# ControllerV0.net
KiCad netlist of a schematic drawn in Altium Designer
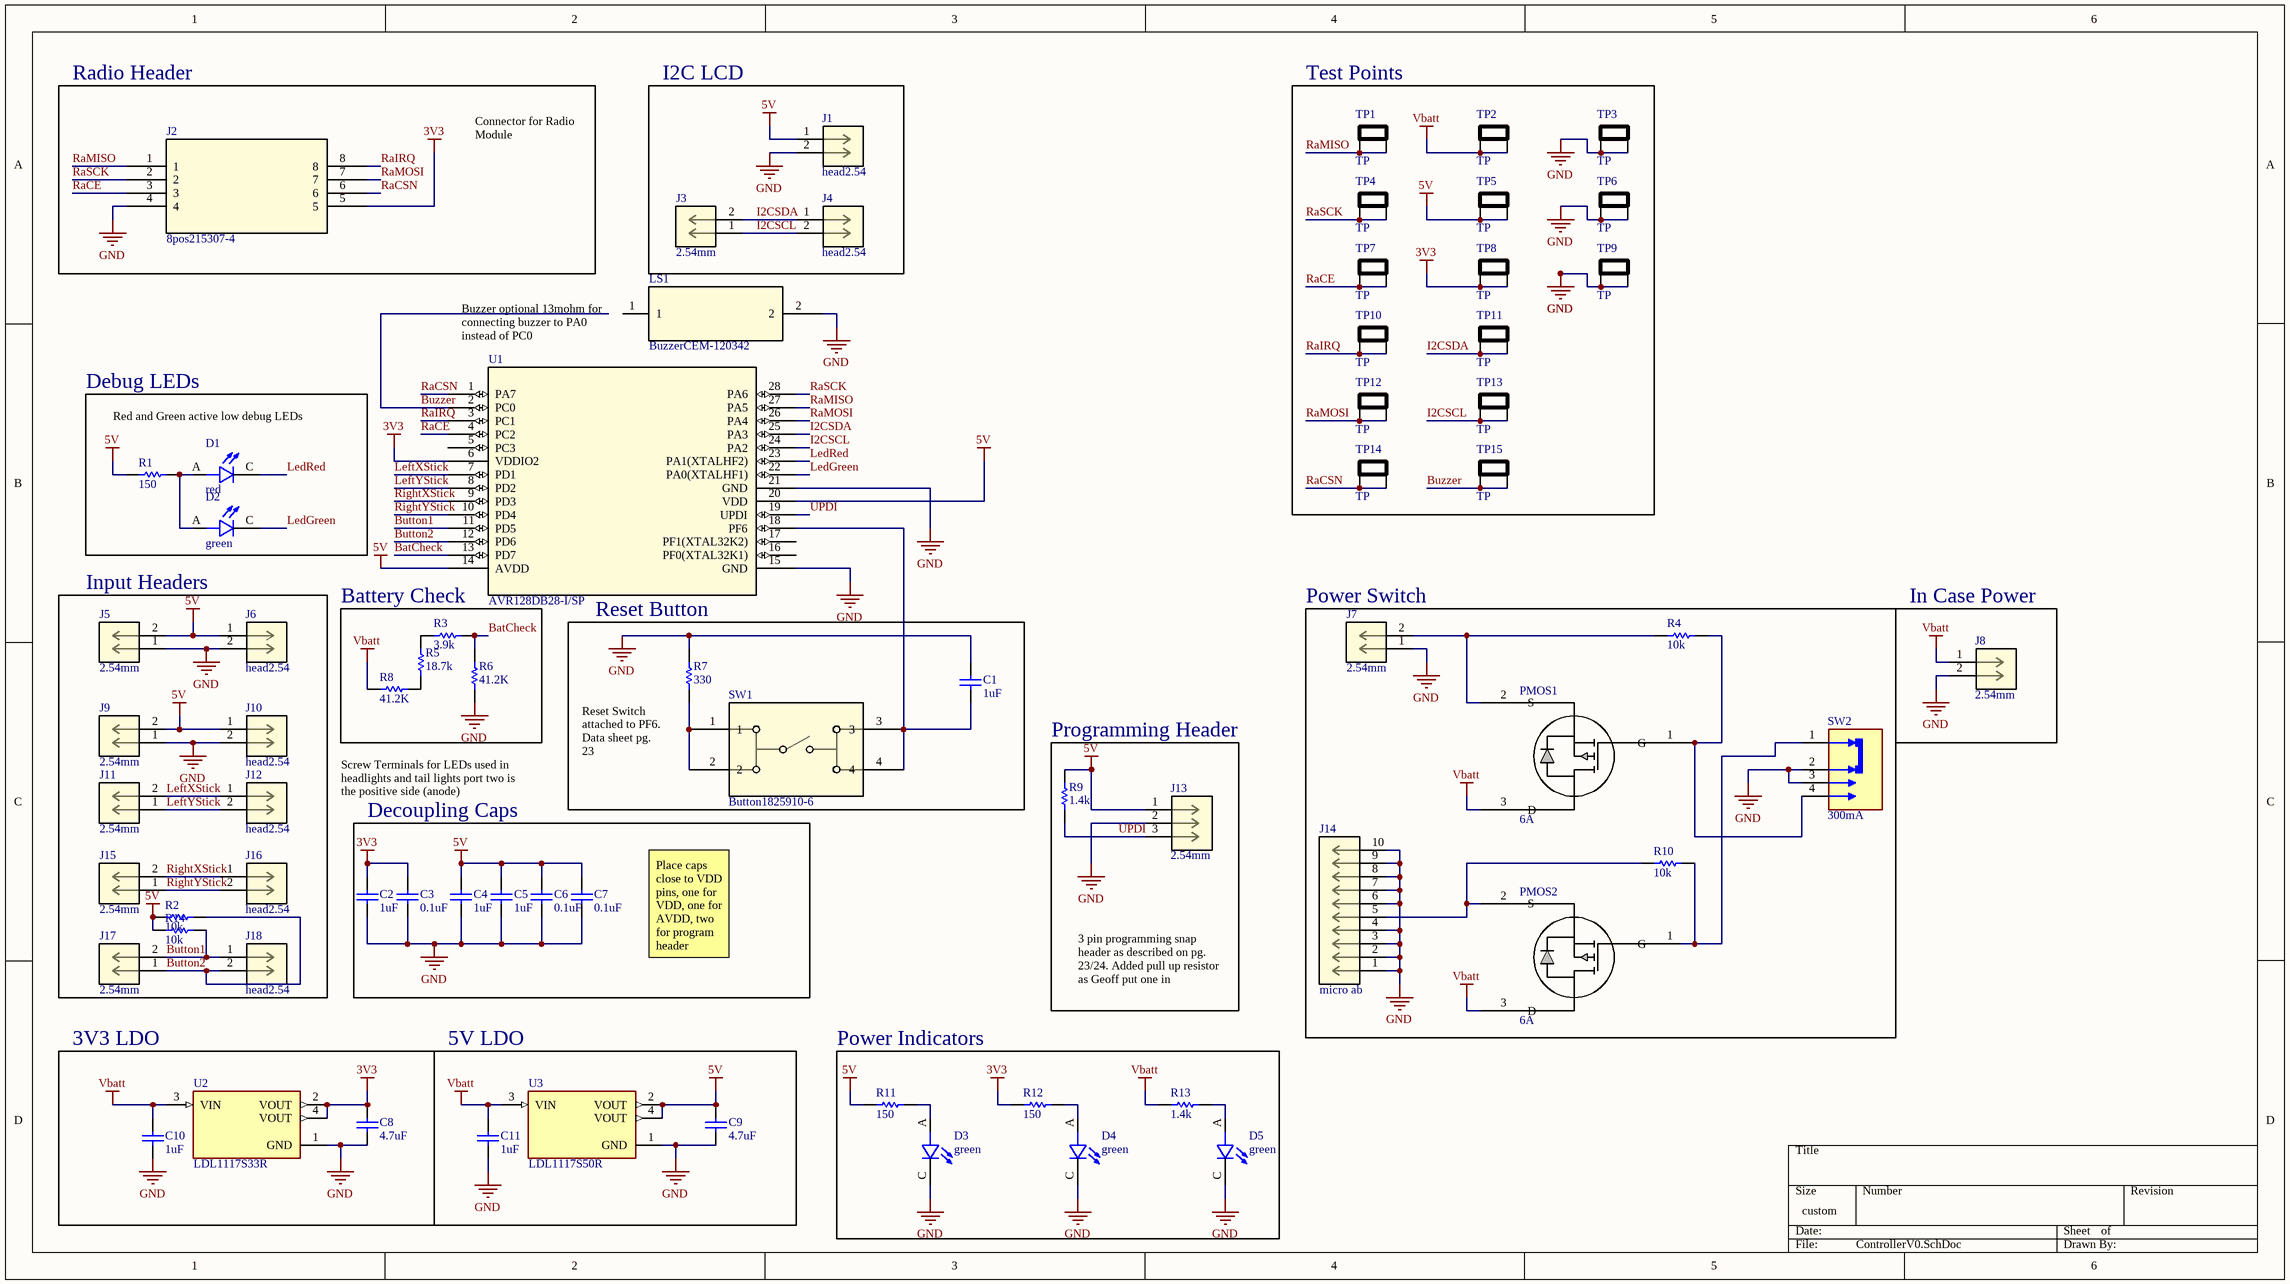
[diagram p0: ControllerV0.SchDoc]

(export (version "E")
  (design (tool "Eeschema 10.0.6"))
  (components
    (comp (ref "C1")
      (value "1uF")
      (footprint "RES 0805")
      (fields
        (field (name "MANUFACTURER") "Samsung")
        (field (name "MANUFACTURER PART NUMBER") "CL21B105KBFNNNE")
      )
      (libsource (lib "Schlib1") (part "CAP CER 1uF 10% 50V 0805"))
    )
    (comp (ref "C2")
      (value "1uF")
      (footprint "RES 0805")
      (fields
        (field (name "MANUFACTURER") "Samsung")
        (field (name "MANUFACTURER PART NUMBER") "CL21B105KBFNNNE")
      )
      (libsource (lib "Schlib1") (part "CAP CER 1uF 10% 50V 0805"))
    )
    (comp (ref "C3")
      (value "0.1uF")
      (footprint "RES 0805")
      (fields
        (field (name "MANUFACTURER") "Yageo")
        (field (name "MANUFACTURER PART NUMBER") "CC0805KRX7R9BB104")
      )
      (libsource (lib "Schlib1") (part "CAP CER 0.1uF 10% 50V 0805"))
    )
    (comp (ref "C4")
      (value "1uF")
      (footprint "RES 0805")
      (fields
        (field (name "MANUFACTURER") "Samsung")
        (field (name "MANUFACTURER PART NUMBER") "CL21B105KBFNNNE")
      )
      (libsource (lib "Schlib1") (part "CAP CER 1uF 10% 50V 0805"))
    )
    (comp (ref "C5")
      (value "1uF")
      (footprint "RES 0805")
      (fields
        (field (name "MANUFACTURER") "Samsung")
        (field (name "MANUFACTURER PART NUMBER") "CL21B105KBFNNNE")
      )
      (libsource (lib "Schlib1") (part "CAP CER 1uF 10% 50V 0805"))
    )
    (comp (ref "C6")
      (value "0.1uF")
      (footprint "RES 0805")
      (fields
        (field (name "MANUFACTURER") "Yageo")
        (field (name "MANUFACTURER PART NUMBER") "CC0805KRX7R9BB104")
      )
      (libsource (lib "Schlib1") (part "CAP CER 0.1uF 10% 50V 0805"))
    )
    (comp (ref "C7")
      (value "0.1uF")
      (footprint "RES 0805")
      (fields
        (field (name "MANUFACTURER") "Yageo")
        (field (name "MANUFACTURER PART NUMBER") "CC0805KRX7R9BB104")
      )
      (libsource (lib "Schlib1") (part "CAP CER 0.1uF 10% 50V 0805"))
    )
    (comp (ref "C8")
      (value "4.7uF")
      (footprint "RES 0805")
      (fields
        (field (name "MANUFACTURER") "Samsung")
        (field (name "MANUFACTURER PART NUMBER") "CL21A475KAQNNNE")
      )
      (libsource (lib "Schlib1") (part "CAP CER 4.7uF 10% 25V 0805"))
    )
    (comp (ref "C9")
      (value "4.7uF")
      (footprint "RES 0805")
      (fields
        (field (name "MANUFACTURER") "Samsung")
        (field (name "MANUFACTURER PART NUMBER") "CL21A475KAQNNNE")
      )
      (libsource (lib "Schlib1") (part "CAP CER 4.7uF 10% 25V 0805"))
    )
    (comp (ref "C10")
      (value "1uF")
      (footprint "RES 0805")
      (fields
        (field (name "MANUFACTURER") "Samsung")
        (field (name "MANUFACTURER PART NUMBER") "CL21B105KBFNNNE")
      )
      (libsource (lib "Schlib1") (part "CAP CER 1uF 10% 50V 0805"))
    )
    (comp (ref "C11")
      (value "1uF")
      (footprint "RES 0805")
      (fields
        (field (name "MANUFACTURER") "Samsung")
        (field (name "MANUFACTURER PART NUMBER") "CL21B105KBFNNNE")
      )
      (libsource (lib "Schlib1") (part "CAP CER 1uF 10% 50V 0805"))
    )
    (comp (ref "D1")
      (value "red")
      (footprint "0603LED")
      (description "Single Color LED, Red, Diffused Milky White, 1.2mm")
      (fields (field (name "MANUFACTURER") "Rohm") (field (name "MANUFACTURER PART NUMBER") "SML-D12U1WT86"))
      (libsource (lib "Schlib1") (part "LED redSML-D12U1WT86"))
    )
    (comp (ref "D2")
      (value "green")
      (footprint "0603LED")
      (description "Single Color LED, Pure Green, Diffused Milky White, 1.2mm")
      (fields (field (name "MANUFACTURER") "Rohm") (field (name "MANUFACTURER PART NUMBER") "SML-D12P8WT86"))
      (libsource (lib "Schlib1") (part "LED greenSML-D12P8WT86"))
    )
    (comp (ref "D3")
      (value "green")
      (footprint "0603LED")
      (description "Single Color LED, Pure Green, Diffused Milky White, 1.2mm")
      (fields (field (name "MANUFACTURER") "Rohm") (field (name "MANUFACTURER PART NUMBER") "SML-D12P8WT86"))
      (libsource (lib "Schlib1") (part "LED greenSML-D12P8WT86"))
    )
    (comp (ref "D4")
      (value "green")
      (footprint "0603LED")
      (description "Single Color LED, Pure Green, Diffused Milky White, 1.2mm")
      (fields (field (name "MANUFACTURER") "Rohm") (field (name "MANUFACTURER PART NUMBER") "SML-D12P8WT86"))
      (libsource (lib "Schlib1") (part "LED greenSML-D12P8WT86"))
    )
    (comp (ref "D5")
      (value "green")
      (footprint "0603LED")
      (description "Single Color LED, Pure Green, Diffused Milky White, 1.2mm")
      (fields (field (name "MANUFACTURER") "Rohm") (field (name "MANUFACTURER PART NUMBER") "SML-D12P8WT86"))
      (libsource (lib "Schlib1") (part "LED greenSML-D12P8WT86"))
    )
    (comp (ref "J1")
      (value "head2.54")
      (footprint "Head 2.54mm 2pos")
      (fields (field (name "MANUFACTURER") "Samtec") (field (name "MANUFACTURER PART NUMBER") "TS-102-G-AA"))
      (libsource (lib "Schlib1") (part "HEAD 2.54mm 2pos"))
    )
    (comp (ref "J2")
      (value "8pos215307-4")
      (footprint "215307-4")
      (fields
        (field (name "MANUFACTURER") "TE Connectivity")
        (field (name "MANUFACTURER PART NUMBER") "215307-4")
      )
      (libsource (lib "Schlib1") (part "8pos215307-4"))
    )
    (comp (ref "J3")
      (value "2.54mm")
      (footprint "CON screw 2pos 2.54mm")
      (description "Barrier Strip Terminal Block, 6A, 1 Row(s), 1 Deck(s)")
      (fields
        (field (name "MANUFACTURER") "On-Shore Technology")
        (field (name "MANUFACTURER PART NUMBER") "OSTVN02A150")
        (field (name "SAFETY APPROVAL") "UL,CUL")
      )
      (libsource (lib "Schlib1") (part "CON screw 2pos 2.54mm"))
    )
    (comp (ref "J4")
      (value "head2.54")
      (footprint "Head 2.54mm 2pos")
      (fields (field (name "MANUFACTURER") "Samtec") (field (name "MANUFACTURER PART NUMBER") "TS-102-G-AA"))
      (libsource (lib "Schlib1") (part "HEAD 2.54mm 2pos"))
    )
    (comp (ref "J5")
      (value "2.54mm")
      (footprint "CON screw 2pos 2.54mm")
      (description "Barrier Strip Terminal Block, 6A, 1 Row(s), 1 Deck(s)")
      (fields
        (field (name "MANUFACTURER") "On-Shore Technology")
        (field (name "MANUFACTURER PART NUMBER") "OSTVN02A150")
        (field (name "SAFETY APPROVAL") "UL,CUL")
      )
      (libsource (lib "Schlib1") (part "CON screw 2pos 2.54mm"))
    )
    (comp (ref "J6")
      (value "head2.54")
      (footprint "Head 2.54mm 2pos")
      (fields (field (name "MANUFACTURER") "Samtec") (field (name "MANUFACTURER PART NUMBER") "TS-102-G-AA"))
      (libsource (lib "Schlib1") (part "HEAD 2.54mm 2pos"))
    )
    (comp (ref "J7")
      (value "2.54mm")
      (footprint "CON screw 2pos 2.54mm")
      (description "Barrier Strip Terminal Block, 6A, 1 Row(s), 1 Deck(s)")
      (fields
        (field (name "MANUFACTURER") "On-Shore Technology")
        (field (name "MANUFACTURER PART NUMBER") "OSTVN02A150")
        (field (name "SAFETY APPROVAL") "UL,CUL")
      )
      (libsource (lib "Schlib1") (part "CON screw 2pos 2.54mm"))
    )
    (comp (ref "J8")
      (value "2.54mm")
      (footprint "CON screw 2pos 2.54mm")
      (description "Barrier Strip Terminal Block, 6A, 1 Row(s), 1 Deck(s)")
      (fields
        (field (name "MANUFACTURER") "On-Shore Technology")
        (field (name "MANUFACTURER PART NUMBER") "OSTVN02A150")
        (field (name "SAFETY APPROVAL") "UL,CUL")
      )
      (libsource (lib "") (part "CON screw 2pos 2.54mm_1"))
    )
    (comp (ref "J9")
      (value "2.54mm")
      (footprint "CON screw 2pos 2.54mm")
      (description "Barrier Strip Terminal Block, 6A, 1 Row(s), 1 Deck(s)")
      (fields
        (field (name "MANUFACTURER") "On-Shore Technology")
        (field (name "MANUFACTURER PART NUMBER") "OSTVN02A150")
        (field (name "SAFETY APPROVAL") "UL,CUL")
      )
      (libsource (lib "Schlib1") (part "CON screw 2pos 2.54mm"))
    )
    (comp (ref "J10")
      (value "head2.54")
      (footprint "Head 2.54mm 2pos")
      (fields (field (name "MANUFACTURER") "Samtec") (field (name "MANUFACTURER PART NUMBER") "TS-102-G-AA"))
      (libsource (lib "Schlib1") (part "HEAD 2.54mm 2pos"))
    )
    (comp (ref "J11")
      (value "2.54mm")
      (footprint "CON screw 2pos 2.54mm")
      (description "Barrier Strip Terminal Block, 6A, 1 Row(s), 1 Deck(s)")
      (fields
        (field (name "MANUFACTURER") "On-Shore Technology")
        (field (name "MANUFACTURER PART NUMBER") "OSTVN02A150")
        (field (name "SAFETY APPROVAL") "UL,CUL")
      )
      (libsource (lib "Schlib1") (part "CON screw 2pos 2.54mm"))
    )
    (comp (ref "J12")
      (value "head2.54")
      (footprint "Head 2.54mm 2pos")
      (fields (field (name "MANUFACTURER") "Samtec") (field (name "MANUFACTURER PART NUMBER") "TS-102-G-AA"))
      (libsource (lib "Schlib1") (part "HEAD 2.54mm 2pos"))
    )
    (comp (ref "J13")
      (value "2.54mm")
      (footprint "HEAD 2.54mm 3pos")
      (fields (field (name "MANUFACTURER") "Samtec") (field (name "MANUFACTURER PART NUMBER") "TS-103-T-A"))
      (libsource (lib "Schlib1") (part "HEAD 2.54mm 3pos"))
    )
    (comp (ref "J14")
      (value "micro ab")
      (footprint "USB micro ab 0475900001")
      (description "USB Connector, 5 Contact(s), Female, Right Angle, Surface Mount Terminal, Locking, Receptacle")
      (fields (field (name "MANUFACTURER") "Molex") (field (name "MANUFACTURER PART NUMBER") "47590-0001"))
      (libsource (lib "Schlib1") (part "CON USB micro ab"))
    )
    (comp (ref "J15")
      (value "2.54mm")
      (footprint "CON screw 2pos 2.54mm")
      (description "Barrier Strip Terminal Block, 6A, 1 Row(s), 1 Deck(s)")
      (fields
        (field (name "MANUFACTURER") "On-Shore Technology")
        (field (name "MANUFACTURER PART NUMBER") "OSTVN02A150")
        (field (name "SAFETY APPROVAL") "UL,CUL")
      )
      (libsource (lib "Schlib1") (part "CON screw 2pos 2.54mm"))
    )
    (comp (ref "J16")
      (value "head2.54")
      (footprint "Head 2.54mm 2pos")
      (fields (field (name "MANUFACTURER") "Samtec") (field (name "MANUFACTURER PART NUMBER") "TS-102-G-AA"))
      (libsource (lib "Schlib1") (part "HEAD 2.54mm 2pos"))
    )
    (comp (ref "J17")
      (value "2.54mm")
      (footprint "CON screw 2pos 2.54mm")
      (description "Barrier Strip Terminal Block, 6A, 1 Row(s), 1 Deck(s)")
      (fields
        (field (name "MANUFACTURER") "On-Shore Technology")
        (field (name "MANUFACTURER PART NUMBER") "OSTVN02A150")
        (field (name "SAFETY APPROVAL") "UL,CUL")
      )
      (libsource (lib "Schlib1") (part "CON screw 2pos 2.54mm"))
    )
    (comp (ref "J18")
      (value "head2.54")
      (footprint "Head 2.54mm 2pos")
      (fields (field (name "MANUFACTURER") "Samtec") (field (name "MANUFACTURER PART NUMBER") "TS-102-G-AA"))
      (libsource (lib "Schlib1") (part "HEAD 2.54mm 2pos"))
    )
    (comp (ref "LS1")
      (value "BuzzerCEM-120342")
      (footprint "CEM-1203(42)")
      (description "Audio Signaling/Alarm Devices")
      (fields
        (field (name "MANUFACTURER") "CUI Devices")
        (field (name "MANUFACTURER PART NUMBER") "CEM-1203(42)")
      )
      (libsource (lib "Schlib1") (part "BuzzerCEM-120342"))
    )
    (comp (ref "PMOS1")
      (value "6A")
      (footprint "SOT-23F MOS PMOS 30V 6A")
      (fields
        (field (name "MANUFACTURER") "Toshiba")
        (field (name "MANUFACTURER PART NUMBER") "SSM3J372R,LF")
      )
      (libsource (lib "Schlib1") (part "MOS PMOS 30V 6A"))
    )
    (comp (ref "PMOS2")
      (value "6A")
      (footprint "SOT-23F MOS PMOS 30V 6A")
      (fields
        (field (name "MANUFACTURER") "Toshiba")
        (field (name "MANUFACTURER PART NUMBER") "SSM3J372R,LF")
      )
      (libsource (lib "Schlib1") (part "MOS PMOS 30V 6A"))
    )
    (comp (ref "R1")
      (value "150")
      (footprint "RES 0805")
      (fields
        (field (name "MANUFACTURER") "Yageo")
        (field (name "MANUFACTURER PART NUMBER") "RC0805FR-07150RL")
        (field (name "TOLERANCE") "1%")
      )
      (libsource (lib "Schlib1") (part "RES 150 1% 0.125 0805"))
    )
    (comp (ref "R2")
      (value "10k")
      (footprint "RES 0805")
      (fields
        (field (name "MANUFACTURER") "Stackpole Electronics")
        (field (name "MANUFACTURER PART NUMBER") "RMCF0805FT10K0")
        (field (name "TOLERANCE") "1%")
      )
      (libsource (lib "Schlib1") (part "RES 10k 1% 0.125 0805"))
    )
    (comp (ref "R3")
      (value "3.9k")
      (footprint "RES 0805")
      (fields
        (field (name "MANUFACTURER") "Stackpole Electronics")
        (field (name "MANUFACTURER PART NUMBER") "RMCF0805FT3K92")
        (field (name "TOLERANCE") "1%")
      )
      (libsource (lib "Schlib1") (part "RES 3.9k 1% 0.125W 0805"))
    )
    (comp (ref "R4")
      (value "10k")
      (footprint "RES 0805")
      (fields
        (field (name "MANUFACTURER") "Stackpole Electronics")
        (field (name "MANUFACTURER PART NUMBER") "RMCF0805FT10K0")
        (field (name "TOLERANCE") "1%")
      )
      (libsource (lib "Schlib1") (part "RES 10k 1% 0.125 0805"))
    )
    (comp (ref "R5")
      (value "18.7k")
      (footprint "RES 0805")
      (fields
        (field (name "MANUFACTURER") "Stackpole Electronics")
        (field (name "MANUFACTURER PART NUMBER") "RMCF0805FT18K7")
        (field (name "TOLERANCE") "1%")
      )
      (libsource (lib "Schlib1") (part "RES 18.7k 1% 0.125W 0805"))
    )
    (comp (ref "R6")
      (value "41.2K")
      (footprint "RES 0805")
      (fields
        (field (name "MANUFACTURER") "Vishay")
        (field (name "MANUFACTURER PART NUMBER") "CRCW080541K2FKEA")
        (field (name "TOLERANCE") "1%")
      )
      (libsource (lib "Schlib1") (part "RES 41.2K 1% 0.125W 0805"))
    )
    (comp (ref "R7")
      (value "330")
      (footprint "RES 0805")
      (fields
        (field (name "MANUFACTURER") "Stackpole Electronics")
        (field (name "MANUFACTURER PART NUMBER") "RMCF0805FT330R")
        (field (name "TOLERANCE") "1%")
      )
      (libsource (lib "Schlib1") (part "RES 330 1% 0.125W 0805"))
    )
    (comp (ref "R8")
      (value "41.2K")
      (footprint "RES 0805")
      (fields
        (field (name "MANUFACTURER") "Vishay")
        (field (name "MANUFACTURER PART NUMBER") "CRCW080541K2FKEA")
        (field (name "TOLERANCE") "1%")
      )
      (libsource (lib "Schlib1") (part "RES 41.2K 1% 0.125W 0805"))
    )
    (comp (ref "R9")
      (value "1.4k")
      (footprint "RES 0805")
      (fields
        (field (name "MANUFACTURER") "Yageo")
        (field (name "MANUFACTURER PART NUMBER") "RC0805FR-071K4L")
        (field (name "TOLERANCE") "1%")
      )
      (libsource (lib "Schlib1") (part "RES 1.4k 1% 0.125W 0805"))
    )
    (comp (ref "R10")
      (value "10k")
      (footprint "RES 0805")
      (fields
        (field (name "MANUFACTURER") "Stackpole Electronics")
        (field (name "MANUFACTURER PART NUMBER") "RMCF0805FT10K0")
        (field (name "TOLERANCE") "1%")
      )
      (libsource (lib "Schlib1") (part "RES 10k 1% 0.125 0805"))
    )
    (comp (ref "R11")
      (value "150")
      (footprint "RES 0805")
      (fields
        (field (name "MANUFACTURER") "Yageo")
        (field (name "MANUFACTURER PART NUMBER") "RC0805FR-07150RL")
        (field (name "TOLERANCE") "1%")
      )
      (libsource (lib "Schlib1") (part "RES 150 1% 0.125 0805"))
    )
    (comp (ref "R12")
      (value "150")
      (footprint "RES 0805")
      (fields
        (field (name "MANUFACTURER") "Yageo")
        (field (name "MANUFACTURER PART NUMBER") "RC0805FR-07150RL")
        (field (name "TOLERANCE") "1%")
      )
      (libsource (lib "Schlib1") (part "RES 150 1% 0.125 0805"))
    )
    (comp (ref "R13")
      (value "1.4k")
      (footprint "RES 0805")
      (fields
        (field (name "MANUFACTURER") "Yageo")
        (field (name "MANUFACTURER PART NUMBER") "RC0805FR-071K4L")
        (field (name "TOLERANCE") "1%")
      )
      (libsource (lib "Schlib1") (part "RES 1.4k 1% 0.125W 0805"))
    )
    (comp (ref "R14")
      (value "10k")
      (footprint "RES 0805")
      (fields
        (field (name "MANUFACTURER") "Stackpole Electronics")
        (field (name "MANUFACTURER PART NUMBER") "RMCF0805FT10K0")
        (field (name "TOLERANCE") "1%")
      )
      (libsource (lib "Schlib1") (part "RES 10k 1% 0.125 0805"))
    )
    (comp (ref "SW1")
      (value "Button1825910-6")
      (footprint "Button1825910-6")
      (fields
        (field (name "MANUFACTURER") "TE Connectivity Alcoswitch")
        (field (name "MANUFACTURER PART NUMBER") "1825910-6")
      )
      (libsource (lib "Schlib1") (part "Button1825910-6"))
    )
    (comp (ref "SW2")
      (value "300mA")
      (footprint "Switch On-On-On 300mA SLW-1277545-2A-RA-S-D")
      (description "12.7 x 7.5 x 4.5 mm, 2 mm Raised Slide Actuator, Right Angle, Through Hole, Slide Switch")
      (fields
        (field (name "MANUFACTURER") "Same Sky")
        (field (name "MANUFACTURER PART NUMBER") "SLW-1277545-2A-RA-S-D")
      )
      (libsource (lib "Schlib1") (part "SW On-On-On 300mA"))
    )
    (comp (ref "TP1")
      (value "TP")
      (footprint "RES 0805")
      (description "Testing/Accessories")
      (fields (field (name "MANUFACTURER") "KOA Speer") (field (name "MANUFACTURER PART NUMBER") "RCTCTE"))
      (libsource (lib "Schlib1") (part "TP clip 0805 RCTCTE"))
    )
    (comp (ref "TP2")
      (value "TP")
      (footprint "RES 0805")
      (description "Testing/Accessories")
      (fields (field (name "MANUFACTURER") "KOA Speer") (field (name "MANUFACTURER PART NUMBER") "RCTCTE"))
      (libsource (lib "Schlib1") (part "TP clip 0805 RCTCTE"))
    )
    (comp (ref "TP3")
      (value "TP")
      (footprint "RES 0805")
      (description "Testing/Accessories")
      (fields (field (name "MANUFACTURER") "KOA Speer") (field (name "MANUFACTURER PART NUMBER") "RCTCTE"))
      (libsource (lib "Schlib1") (part "TP clip 0805 RCTCTE"))
    )
    (comp (ref "TP4")
      (value "TP")
      (footprint "RES 0805")
      (description "Testing/Accessories")
      (fields (field (name "MANUFACTURER") "KOA Speer") (field (name "MANUFACTURER PART NUMBER") "RCTCTE"))
      (libsource (lib "Schlib1") (part "TP clip 0805 RCTCTE"))
    )
    (comp (ref "TP5")
      (value "TP")
      (footprint "RES 0805")
      (description "Testing/Accessories")
      (fields (field (name "MANUFACTURER") "KOA Speer") (field (name "MANUFACTURER PART NUMBER") "RCTCTE"))
      (libsource (lib "Schlib1") (part "TP clip 0805 RCTCTE"))
    )
    (comp (ref "TP6")
      (value "TP")
      (footprint "RES 0805")
      (description "Testing/Accessories")
      (fields (field (name "MANUFACTURER") "KOA Speer") (field (name "MANUFACTURER PART NUMBER") "RCTCTE"))
      (libsource (lib "Schlib1") (part "TP clip 0805 RCTCTE"))
    )
    (comp (ref "TP7")
      (value "TP")
      (footprint "RES 0805")
      (description "Testing/Accessories")
      (fields (field (name "MANUFACTURER") "KOA Speer") (field (name "MANUFACTURER PART NUMBER") "RCTCTE"))
      (libsource (lib "Schlib1") (part "TP clip 0805 RCTCTE"))
    )
    (comp (ref "TP8")
      (value "TP")
      (footprint "RES 0805")
      (description "Testing/Accessories")
      (fields (field (name "MANUFACTURER") "KOA Speer") (field (name "MANUFACTURER PART NUMBER") "RCTCTE"))
      (libsource (lib "Schlib1") (part "TP clip 0805 RCTCTE"))
    )
    (comp (ref "TP9")
      (value "TP")
      (footprint "RES 0805")
      (description "Testing/Accessories")
      (fields (field (name "MANUFACTURER") "KOA Speer") (field (name "MANUFACTURER PART NUMBER") "RCTCTE"))
      (libsource (lib "Schlib1") (part "TP clip 0805 RCTCTE"))
    )
    (comp (ref "TP10")
      (value "TP")
      (footprint "RES 0805")
      (description "Testing/Accessories")
      (fields (field (name "MANUFACTURER") "KOA Speer") (field (name "MANUFACTURER PART NUMBER") "RCTCTE"))
      (libsource (lib "Schlib1") (part "TP clip 0805 RCTCTE"))
    )
    (comp (ref "TP11")
      (value "TP")
      (footprint "RES 0805")
      (description "Testing/Accessories")
      (fields (field (name "MANUFACTURER") "KOA Speer") (field (name "MANUFACTURER PART NUMBER") "RCTCTE"))
      (libsource (lib "Schlib1") (part "TP clip 0805 RCTCTE"))
    )
    (comp (ref "TP12")
      (value "TP")
      (footprint "RES 0805")
      (description "Testing/Accessories")
      (fields (field (name "MANUFACTURER") "KOA Speer") (field (name "MANUFACTURER PART NUMBER") "RCTCTE"))
      (libsource (lib "Schlib1") (part "TP clip 0805 RCTCTE"))
    )
    (comp (ref "TP13")
      (value "TP")
      (footprint "RES 0805")
      (description "Testing/Accessories")
      (fields (field (name "MANUFACTURER") "KOA Speer") (field (name "MANUFACTURER PART NUMBER") "RCTCTE"))
      (libsource (lib "Schlib1") (part "TP clip 0805 RCTCTE"))
    )
    (comp (ref "TP14")
      (value "TP")
      (footprint "RES 0805")
      (description "Testing/Accessories")
      (fields (field (name "MANUFACTURER") "KOA Speer") (field (name "MANUFACTURER PART NUMBER") "RCTCTE"))
      (libsource (lib "Schlib1") (part "TP clip 0805 RCTCTE"))
    )
    (comp (ref "TP15")
      (value "TP")
      (footprint "RES 0805")
      (description "Testing/Accessories")
      (fields (field (name "MANUFACTURER") "KOA Speer") (field (name "MANUFACTURER PART NUMBER") "RCTCTE"))
      (libsource (lib "Schlib1") (part "TP clip 0805 RCTCTE"))
    )
    (comp (ref "U1")
      (value "AVR128DB28-I/SP")
      (footprint "AVR128DB28-ISP")
      (description "RISC Microcontroller, 8-Bit, FLASH, AVR CPU, 24MHz, CMOS, PDIP28")
      (fields (field (name "MANUFACTURER") "Microchip"))
      (libsource (lib "Schlib1") (part "AVR128DB28-I/SP"))
    )
    (comp (ref "U2")
      (value "LDL1117S33R")
      (footprint "SOT230P700X180-4N")
      (description "Fixed Positive LDO Regulator, 3.3V, 0.6V Dropout, PDSO4")
      (fields (field (name "MANUFACTURER") "STMicroelectronics"))
      (libsource (lib "Schlib1") (part "LDL1117S33R"))
    )
    (comp (ref "U3")
      (value "LDL1117S50R")
      (footprint "SOT230P700X180-4N")
      (description "Fixed Positive LDO Regulator, 5V, 0.6V Dropout, PDSO4")
      (fields (field (name "MANUFACTURER") "STMicroelectronics"))
      (libsource (lib "Schlib1") (part "LDL1117S50R"))
    )
  )
  (nets
    (net (code "1") (name "/BatCheck") (class "Default")
      (node (ref "R3") (pin "2") (pinfunction "2_2") (pintype "passive"))
      (node (ref "R6") (pin "2") (pinfunction "2_2") (pintype "passive"))
      (node (ref "U1") (pin "13") (pinfunction "PD7_13") (pintype "bidirectional"))
    )
    (net (code "2") (name "/Button1") (class "Default")
      (node (ref "J17") (pin "2") (pinfunction "2_2") (pintype "passive"))
      (node (ref "J18") (pin "1") (pinfunction "1_1") (pintype "passive"))
      (node (ref "R14") (pin "1") (pinfunction "1_1") (pintype "passive"))
      (node (ref "U1") (pin "11") (pinfunction "PD5_11") (pintype "bidirectional"))
    )
    (net (code "3") (name "/Button2") (class "Default")
      (node (ref "J17") (pin "1") (pinfunction "1_1") (pintype "passive"))
      (node (ref "J18") (pin "2") (pinfunction "2_2") (pintype "passive"))
      (node (ref "R2") (pin "1") (pinfunction "1_1") (pintype "passive"))
      (node (ref "U1") (pin "12") (pinfunction "PD6_12") (pintype "bidirectional"))
    )
    (net (code "4") (name "/Buzzer") (class "Default")
      (node (ref "LS1") (pin "1") (pinfunction "1_1") (pintype "passive"))
      (node (ref "TP15") (pin "1") (pinfunction "1_1") (pintype "passive"))
      (node (ref "TP15") (pin "2") (pinfunction "2_2") (pintype "passive"))
      (node (ref "U1") (pin "2") (pinfunction "PC0_2") (pintype "bidirectional"))
    )
    (net (code "5") (name "/I2CSCL") (class "Default")
      (node (ref "J3") (pin "1") (pinfunction "1_1") (pintype "passive"))
      (node (ref "J4") (pin "2") (pinfunction "2_2") (pintype "passive"))
      (node (ref "TP13") (pin "1") (pinfunction "1_1") (pintype "passive"))
      (node (ref "TP13") (pin "2") (pinfunction "2_2") (pintype "passive"))
      (node (ref "U1") (pin "24") (pinfunction "PA2_24") (pintype "bidirectional"))
    )
    (net (code "6") (name "/I2CSDA") (class "Default")
      (node (ref "J3") (pin "2") (pinfunction "2_2") (pintype "passive"))
      (node (ref "J4") (pin "1") (pinfunction "1_1") (pintype "passive"))
      (node (ref "TP11") (pin "1") (pinfunction "1_1") (pintype "passive"))
      (node (ref "TP11") (pin "2") (pinfunction "2_2") (pintype "passive"))
      (node (ref "U1") (pin "25") (pinfunction "PA3_25") (pintype "bidirectional"))
    )
    (net (code "7") (name "/LedGreen") (class "Default")
      (node (ref "D2") (pin "C") (pinfunction "C_C") (pintype "passive"))
      (node (ref "U1") (pin "22") (pinfunction "PA0(XTALHF1)_22") (pintype "bidirectional"))
    )
    (net (code "8") (name "/LedRed") (class "Default")
      (node (ref "D1") (pin "C") (pinfunction "C_C") (pintype "passive"))
      (node (ref "U1") (pin "23") (pinfunction "PA1(XTALHF2)_23") (pintype "bidirectional"))
    )
    (net (code "9") (name "/LeftXStick") (class "Default")
      (node (ref "J11") (pin "2") (pinfunction "2_2") (pintype "passive"))
      (node (ref "J12") (pin "1") (pinfunction "1_1") (pintype "passive"))
      (node (ref "U1") (pin "7") (pinfunction "PD1_7") (pintype "bidirectional"))
    )
    (net (code "10") (name "/LeftYStick") (class "Default")
      (node (ref "J11") (pin "1") (pinfunction "1_1") (pintype "passive"))
      (node (ref "J12") (pin "2") (pinfunction "2_2") (pintype "passive"))
      (node (ref "U1") (pin "8") (pinfunction "PD2_8") (pintype "bidirectional"))
    )
    (net (code "11") (name "/RaCE") (class "Default")
      (node (ref "J2") (pin "3") (pinfunction "3_3") (pintype "passive"))
      (node (ref "TP7") (pin "1") (pinfunction "1_1") (pintype "passive"))
      (node (ref "TP7") (pin "2") (pinfunction "2_2") (pintype "passive"))
      (node (ref "U1") (pin "4") (pinfunction "PC2_4") (pintype "bidirectional"))
    )
    (net (code "12") (name "/RaCSN") (class "Default")
      (node (ref "J2") (pin "6") (pinfunction "6_6") (pintype "passive"))
      (node (ref "TP14") (pin "1") (pinfunction "1_1") (pintype "passive"))
      (node (ref "TP14") (pin "2") (pinfunction "2_2") (pintype "passive"))
      (node (ref "U1") (pin "1") (pinfunction "PA7_1") (pintype "bidirectional"))
    )
    (net (code "13") (name "/RaIRQ") (class "Default")
      (node (ref "J2") (pin "8") (pinfunction "8_8") (pintype "passive"))
      (node (ref "TP10") (pin "1") (pinfunction "1_1") (pintype "passive"))
      (node (ref "TP10") (pin "2") (pinfunction "2_2") (pintype "passive"))
      (node (ref "U1") (pin "3") (pinfunction "PC1_3") (pintype "bidirectional"))
    )
    (net (code "14") (name "/RaMISO") (class "Default")
      (node (ref "J2") (pin "1") (pinfunction "1_1") (pintype "passive"))
      (node (ref "TP1") (pin "1") (pinfunction "1_1") (pintype "passive"))
      (node (ref "TP1") (pin "2") (pinfunction "2_2") (pintype "passive"))
      (node (ref "U1") (pin "27") (pinfunction "PA5_27") (pintype "bidirectional"))
    )
    (net (code "15") (name "/RaMOSI") (class "Default")
      (node (ref "J2") (pin "7") (pinfunction "7_7") (pintype "passive"))
      (node (ref "TP12") (pin "1") (pinfunction "1_1") (pintype "passive"))
      (node (ref "TP12") (pin "2") (pinfunction "2_2") (pintype "passive"))
      (node (ref "U1") (pin "26") (pinfunction "PA4_26") (pintype "bidirectional"))
    )
    (net (code "16") (name "/RaSCK") (class "Default")
      (node (ref "J2") (pin "2") (pinfunction "2_2") (pintype "passive"))
      (node (ref "TP4") (pin "1") (pinfunction "1_1") (pintype "passive"))
      (node (ref "TP4") (pin "2") (pinfunction "2_2") (pintype "passive"))
      (node (ref "U1") (pin "28") (pinfunction "PA6_28") (pintype "bidirectional"))
    )
    (net (code "17") (name "/RightXStick") (class "Default")
      (node (ref "J15") (pin "2") (pinfunction "2_2") (pintype "passive"))
      (node (ref "J16") (pin "1") (pinfunction "1_1") (pintype "passive"))
      (node (ref "U1") (pin "9") (pinfunction "PD3_9") (pintype "bidirectional"))
    )
    (net (code "18") (name "/RightYStick") (class "Default")
      (node (ref "J15") (pin "1") (pinfunction "1_1") (pintype "passive"))
      (node (ref "J16") (pin "2") (pinfunction "2_2") (pintype "passive"))
      (node (ref "U1") (pin "10") (pinfunction "PD4_10") (pintype "bidirectional"))
    )
    (net (code "19") (name "/UPDI") (class "Default")
      (node (ref "J13") (pin "3") (pinfunction "3_3") (pintype "passive"))
      (node (ref "R9") (pin "1") (pinfunction "1_1") (pintype "passive"))
      (node (ref "U1") (pin "19") (pinfunction "UPDI_19") (pintype "bidirectional"))
    )
    (net (code "20") (name "3V3") (class "Default")
      (node (ref "C2") (pin "2") (pinfunction "2_2") (pintype "passive"))
      (node (ref "C3") (pin "2") (pinfunction "2_2") (pintype "passive"))
      (node (ref "C8") (pin "2") (pinfunction "2_2") (pintype "passive"))
      (node (ref "J2") (pin "5") (pinfunction "5_5") (pintype "passive"))
      (node (ref "R12") (pin "1") (pinfunction "1_1") (pintype "passive"))
      (node (ref "TP8") (pin "1") (pinfunction "1_1") (pintype "passive"))
      (node (ref "TP8") (pin "2") (pinfunction "2_2") (pintype "passive"))
      (node (ref "U1") (pin "6") (pinfunction "VDDIO2_6") (pintype "power_in"))
      (node (ref "U2") (pin "2") (pinfunction "VOUT_2") (pintype "output"))
      (node (ref "U2") (pin "4") (pinfunction "VOUT_4") (pintype "output"))
    )
    (net (code "21") (name "5V") (class "Default")
      (node (ref "C4") (pin "2") (pinfunction "2_2") (pintype "passive"))
      (node (ref "C5") (pin "1") (pinfunction "1_1") (pintype "passive"))
      (node (ref "C6") (pin "2") (pinfunction "2_2") (pintype "passive"))
      (node (ref "C7") (pin "2") (pinfunction "2_2") (pintype "passive"))
      (node (ref "C9") (pin "2") (pinfunction "2_2") (pintype "passive"))
      (node (ref "J1") (pin "1") (pinfunction "1_1") (pintype "passive"))
      (node (ref "J10") (pin "1") (pinfunction "1_1") (pintype "passive"))
      (node (ref "J13") (pin "1") (pinfunction "1_1") (pintype "passive"))
      (node (ref "J5") (pin "2") (pinfunction "2_2") (pintype "passive"))
      (node (ref "J6") (pin "1") (pinfunction "1_1") (pintype "passive"))
      (node (ref "J9") (pin "2") (pinfunction "2_2") (pintype "passive"))
      (node (ref "R1") (pin "1") (pinfunction "1_1") (pintype "passive"))
      (node (ref "R11") (pin "1") (pinfunction "1_1") (pintype "passive"))
      (node (ref "R14") (pin "2") (pinfunction "2_2") (pintype "passive"))
      (node (ref "R2") (pin "2") (pinfunction "2_2") (pintype "passive"))
      (node (ref "R9") (pin "2") (pinfunction "2_2") (pintype "passive"))
      (node (ref "TP5") (pin "1") (pinfunction "1_1") (pintype "passive"))
      (node (ref "TP5") (pin "2") (pinfunction "2_2") (pintype "passive"))
      (node (ref "U1") (pin "14") (pinfunction "AVDD_14") (pintype "power_in"))
      (node (ref "U1") (pin "20") (pinfunction "VDD_20") (pintype "power_in"))
      (node (ref "U3") (pin "2") (pinfunction "VOUT_2") (pintype "output"))
      (node (ref "U3") (pin "4") (pinfunction "VOUT_4") (pintype "output"))
    )
    (net (code "22") (name "GND") (class "Default")
      (node (ref "C1") (pin "2") (pinfunction "2_2") (pintype "passive"))
      (node (ref "C10") (pin "1") (pinfunction "1_1") (pintype "passive"))
      (node (ref "C11") (pin "1") (pinfunction "1_1") (pintype "passive"))
      (node (ref "C2") (pin "1") (pinfunction "1_1") (pintype "passive"))
      (node (ref "C3") (pin "1") (pinfunction "1_1") (pintype "passive"))
      (node (ref "C4") (pin "1") (pinfunction "1_1") (pintype "passive"))
      (node (ref "C5") (pin "2") (pinfunction "2_2") (pintype "passive"))
      (node (ref "C6") (pin "1") (pinfunction "1_1") (pintype "passive"))
      (node (ref "C7") (pin "1") (pinfunction "1_1") (pintype "passive"))
      (node (ref "C8") (pin "1") (pinfunction "1_1") (pintype "passive"))
      (node (ref "C9") (pin "1") (pinfunction "1_1") (pintype "passive"))
      (node (ref "D3") (pin "C") (pinfunction "C_C") (pintype "passive"))
      (node (ref "D4") (pin "C") (pinfunction "C_C") (pintype "passive"))
      (node (ref "D5") (pin "C") (pinfunction "C_C") (pintype "passive"))
      (node (ref "J1") (pin "2") (pinfunction "2_2") (pintype "passive"))
      (node (ref "J10") (pin "2") (pinfunction "2_2") (pintype "passive"))
      (node (ref "J13") (pin "2") (pinfunction "2_2") (pintype "passive"))
      (node (ref "J14") (pin "1") (pinfunction "VBUS_1") (pintype "passive"))
      (node (ref "J14") (pin "10") (pinfunction "SHIELD_10") (pintype "power_in"))
      (node (ref "J14") (pin "2") (pinfunction "D-_2") (pintype "passive"))
      (node (ref "J14") (pin "3") (pinfunction "D+_3") (pintype "passive"))
      (node (ref "J14") (pin "4") (pinfunction "ID_4") (pintype "passive"))
      (node (ref "J14") (pin "6") (pinfunction "SHIELD_6") (pintype "power_in"))
      (node (ref "J14") (pin "7") (pinfunction "SHIELD_7") (pintype "power_in"))
      (node (ref "J14") (pin "8") (pinfunction "SHIELD_8") (pintype "power_in"))
      (node (ref "J14") (pin "9") (pinfunction "SHIELD_9") (pintype "power_in"))
      (node (ref "J2") (pin "4") (pinfunction "4_4") (pintype "passive"))
      (node (ref "J5") (pin "1") (pinfunction "1_1") (pintype "passive"))
      (node (ref "J6") (pin "2") (pinfunction "2_2") (pintype "passive"))
      (node (ref "J7") (pin "1") (pinfunction "1_1") (pintype "passive"))
      (node (ref "J8") (pin "2") (pinfunction "2_2") (pintype "passive"))
      (node (ref "J9") (pin "1") (pinfunction "1_1") (pintype "passive"))
      (node (ref "LS1") (pin "2") (pinfunction "2_2") (pintype "passive"))
      (node (ref "R6") (pin "1") (pinfunction "1_1") (pintype "passive"))
      (node (ref "R7") (pin "2") (pinfunction "2_2") (pintype "passive"))
      (node (ref "SW2") (pin "2") (pinfunction "2_2") (pintype "passive"))
      (node (ref "SW2") (pin "3") (pinfunction "3_3") (pintype "passive"))
      (node (ref "TP3") (pin "1") (pinfunction "1_1") (pintype "passive"))
      (node (ref "TP3") (pin "2") (pinfunction "2_2") (pintype "passive"))
      (node (ref "TP6") (pin "1") (pinfunction "1_1") (pintype "passive"))
      (node (ref "TP6") (pin "2") (pinfunction "2_2") (pintype "passive"))
      (node (ref "TP9") (pin "1") (pinfunction "1_1") (pintype "passive"))
      (node (ref "TP9") (pin "2") (pinfunction "2_2") (pintype "passive"))
      (node (ref "U1") (pin "15") (pinfunction "GND_15") (pintype "power_in"))
      (node (ref "U1") (pin "21") (pinfunction "GND_21") (pintype "power_in"))
      (node (ref "U2") (pin "1") (pinfunction "GND_1") (pintype "power_in"))
      (node (ref "U3") (pin "1") (pinfunction "GND_1") (pintype "power_in"))
    )
    (net (code "23") (name "Net-(D1-PadA)") (class "Default")
      (node (ref "D1") (pin "A") (pinfunction "A_A") (pintype "passive"))
      (node (ref "D2") (pin "A") (pinfunction "A_A") (pintype "passive"))
      (node (ref "R1") (pin "2") (pinfunction "2_2") (pintype "passive"))
    )
    (net (code "24") (name "Net-(D3-PadA)") (class "Default")
      (node (ref "D3") (pin "A") (pinfunction "A_A") (pintype "passive"))
      (node (ref "R11") (pin "2") (pinfunction "2_2") (pintype "passive"))
    )
    (net (code "25") (name "Net-(D4-PadA)") (class "Default")
      (node (ref "D4") (pin "A") (pinfunction "A_A") (pintype "passive"))
      (node (ref "R12") (pin "2") (pinfunction "2_2") (pintype "passive"))
    )
    (net (code "26") (name "Net-(D5-PadA)") (class "Default")
      (node (ref "D5") (pin "A") (pinfunction "A_A") (pintype "passive"))
      (node (ref "R13") (pin "2") (pinfunction "2_2") (pintype "passive"))
    )
    (net (code "27") (name "Net-(J14-GND)") (class "Default")
      (node (ref "J14") (pin "5") (pinfunction "GND_5") (pintype "power_in"))
      (node (ref "PMOS2") (pin "2") (pinfunction "S_2") (pintype "passive"))
      (node (ref "R10") (pin "1") (pinfunction "1_1") (pintype "passive"))
    )
    (net (code "28") (name "Net-(PMOS1-G)") (class "Default")
      (node (ref "PMOS1") (pin "1") (pinfunction "G_1") (pintype "passive"))
      (node (ref "R4") (pin "2") (pinfunction "2_2") (pintype "passive"))
      (node (ref "SW2") (pin "4") (pinfunction "4_4") (pintype "passive"))
    )
    (net (code "29") (name "Net-(PMOS1-S)") (class "Default")
      (node (ref "J7") (pin "2") (pinfunction "2_2") (pintype "passive"))
      (node (ref "PMOS1") (pin "2") (pinfunction "S_2") (pintype "passive"))
      (node (ref "R4") (pin "1") (pinfunction "1_1") (pintype "passive"))
    )
    (net (code "30") (name "Net-(PMOS2-G)") (class "Default")
      (node (ref "PMOS2") (pin "1") (pinfunction "G_1") (pintype "passive"))
      (node (ref "R10") (pin "2") (pinfunction "2_2") (pintype "passive"))
      (node (ref "SW2") (pin "1") (pinfunction "1_1") (pintype "passive"))
    )
    (net (code "31") (name "Net-(R3-Pad1)") (class "Default")
      (node (ref "R3") (pin "1") (pinfunction "1_1") (pintype "passive"))
      (node (ref "R5") (pin "1") (pinfunction "1_1") (pintype "passive"))
    )
    (net (code "32") (name "Net-(R5-Pad2)") (class "Default")
      (node (ref "R5") (pin "2") (pinfunction "2_2") (pintype "passive"))
      (node (ref "R8") (pin "1") (pinfunction "1_1") (pintype "passive"))
    )
    (net (code "33") (name "Net-(R7-Pad1)") (class "Default")
      (node (ref "R7") (pin "1") (pinfunction "1_1") (pintype "passive"))
      (node (ref "SW1") (pin "1") (pinfunction "1_1") (pintype "passive"))
      (node (ref "SW1") (pin "2") (pinfunction "2_2") (pintype "passive"))
    )
    (net (code "34") (name "Net-(U1-PF6)") (class "Default")
      (node (ref "C1") (pin "1") (pinfunction "1_1") (pintype "passive"))
      (node (ref "SW1") (pin "3") (pinfunction "3_3") (pintype "passive"))
      (node (ref "SW1") (pin "4") (pinfunction "4_4") (pintype "passive"))
      (node (ref "U1") (pin "18") (pinfunction "PF6_18") (pintype "bidirectional"))
    )
    (net (code "35") (name "Vbatt") (class "Default")
      (node (ref "C10") (pin "2") (pinfunction "2_2") (pintype "passive"))
      (node (ref "C11") (pin "2") (pinfunction "2_2") (pintype "passive"))
      (node (ref "J8") (pin "1") (pinfunction "1_1") (pintype "passive"))
      (node (ref "PMOS1") (pin "3") (pinfunction "D_3") (pintype "passive"))
      (node (ref "PMOS2") (pin "3") (pinfunction "D_3") (pintype "passive"))
      (node (ref "R13") (pin "1") (pinfunction "1_1") (pintype "passive"))
      (node (ref "R8") (pin "2") (pinfunction "2_2") (pintype "passive"))
      (node (ref "TP2") (pin "1") (pinfunction "1_1") (pintype "passive"))
      (node (ref "TP2") (pin "2") (pinfunction "2_2") (pintype "passive"))
      (node (ref "U2") (pin "3") (pinfunction "VIN_3") (pintype "input"))
      (node (ref "U3") (pin "3") (pinfunction "VIN_3") (pintype "input"))
    )
    (net (code "36") (name "unconnected-(U1-PC3-Pad5)") (class "Default")
      (node (ref "U1") (pin "5") (pinfunction "PC3_5") (pintype "bidirectional"))
    )
    (net (code "37") (name "unconnected-(U1-PF0(XTAL32K1)-Pad16)") (class "Default")
      (node (ref "U1") (pin "16") (pinfunction "PF0(XTAL32K1)_16") (pintype "bidirectional"))
    )
    (net (code "38") (name "unconnected-(U1-PF1(XTAL32K2)-Pad17)") (class "Default")
      (node (ref "U1") (pin "17") (pinfunction "PF1(XTAL32K2)_17") (pintype "bidirectional"))
    )
  )
)
